# motor_driver_ver3_0.net
KiCad netlist of a schematic drawn in EAGLE
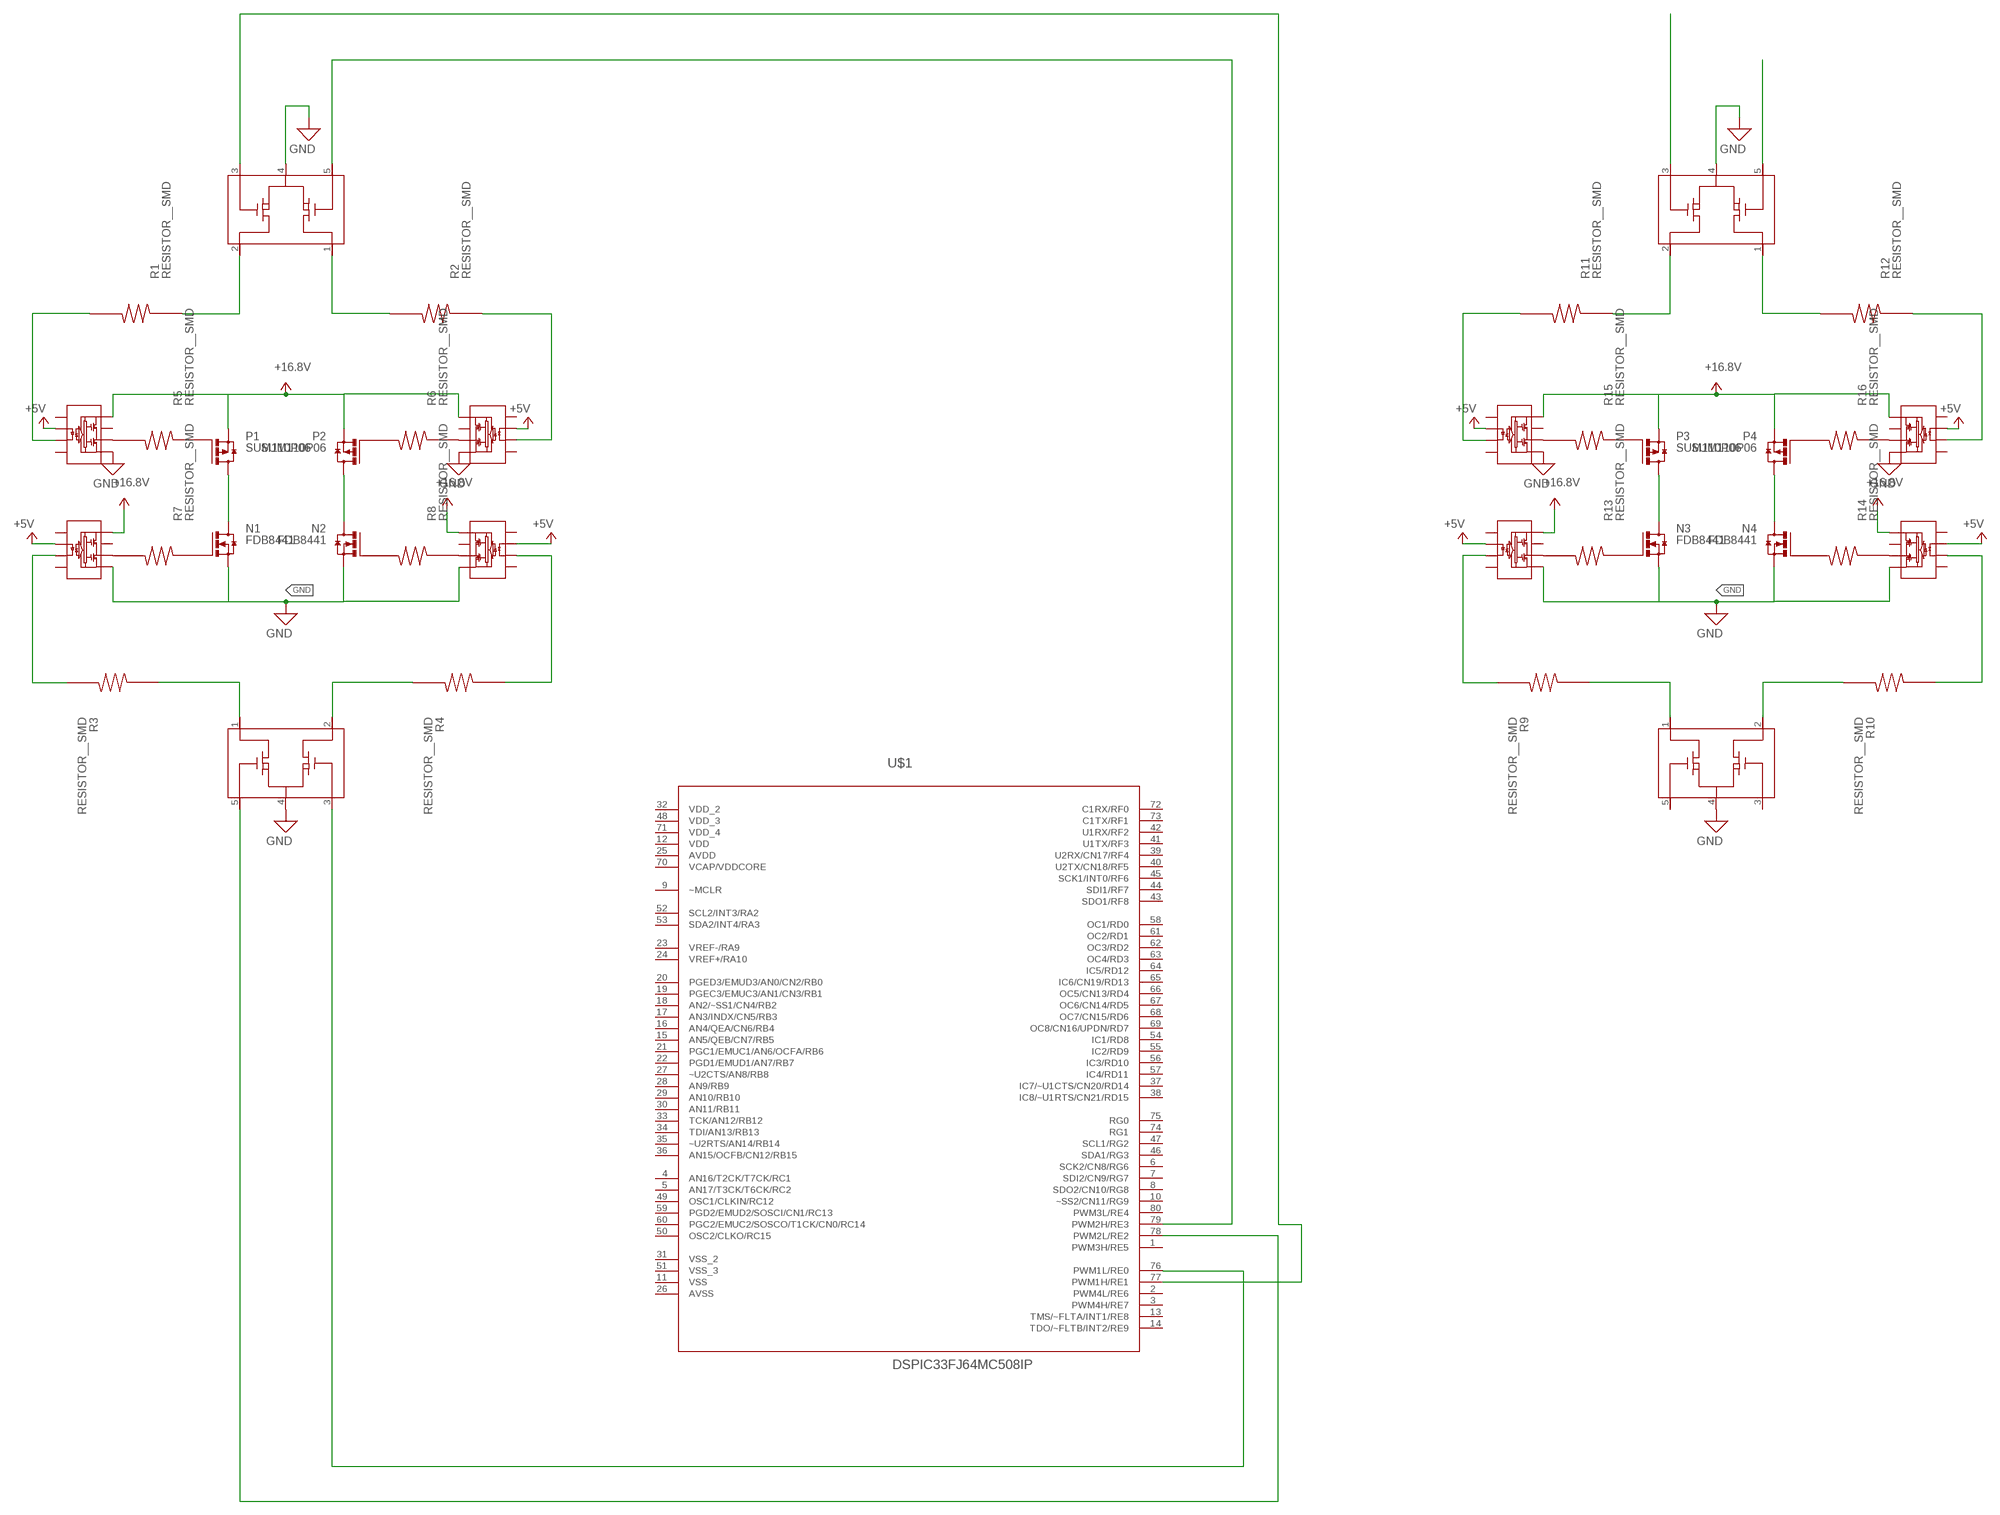
[diagram p0: schematic, sheet 1]

(export (version "E")
  (design (tool "Eeschema 10.0.6"))
  (components
    (comp (ref "F1")
      (value "CPH5617")
      (footprint "eagle-import:CHP-5")
      (libsource (lib "eagle-import") (part "CPH5617"))
    )
    (comp (ref "F2")
      (value "CPH5617")
      (footprint "eagle-import:CHP-5")
      (libsource (lib "eagle-import") (part "CPH5617"))
    )
    (comp (ref "F3")
      (value "CPH5617")
      (footprint "eagle-import:CHP-5")
      (libsource (lib "eagle-import") (part "CPH5617"))
    )
    (comp (ref "F4")
      (value "CPH5617")
      (footprint "eagle-import:CHP-5")
      (libsource (lib "eagle-import") (part "CPH5617"))
    )
    (comp (ref "IC2")
      (value "TLP351")
      (footprint "eagle-import:DIL08")
      (libsource (lib "eagle-import") (part "TLP351"))
    )
    (comp (ref "IC_L_I_D")
      (value "TLP351")
      (footprint "eagle-import:DIL08")
      (libsource (lib "eagle-import") (part "TLP351"))
    )
    (comp (ref "IC_L_I_U")
      (value "TLP351")
      (footprint "eagle-import:DIL08")
      (libsource (lib "eagle-import") (part "TLP351"))
    )
    (comp (ref "IC_L_O_D")
      (value "TLP351")
      (footprint "eagle-import:DIL08")
      (libsource (lib "eagle-import") (part "TLP351"))
    )
    (comp (ref "IC_L_O_U")
      (value "TLP351")
      (footprint "eagle-import:DIL08")
      (libsource (lib "eagle-import") (part "TLP351"))
    )
    (comp (ref "N1")
      (value "FDB8441")
      (footprint "eagle-import:TO-263")
      (libsource (lib "eagle-import") (part "FDB8441"))
    )
    (comp (ref "N2")
      (value "FDB8441")
      (footprint "eagle-import:TO-263")
      (libsource (lib "eagle-import") (part "FDB8441"))
    )
    (comp (ref "N3")
      (value "FDB8441")
      (footprint "eagle-import:TO-263")
      (libsource (lib "eagle-import") (part "FDB8441"))
    )
    (comp (ref "N4")
      (value "FDB8441")
      (footprint "eagle-import:TO-263")
      (libsource (lib "eagle-import") (part "FDB8441"))
    )
    (comp (ref "P1")
      (value "SUM110P06")
      (footprint "eagle-import:TO-263")
      (libsource (lib "eagle-import") (part "SUM110P06"))
    )
    (comp (ref "P2")
      (value "SUM110P06")
      (footprint "eagle-import:TO-263")
      (libsource (lib "eagle-import") (part "SUM110P06"))
    )
    (comp (ref "P3")
      (value "SUM110P06")
      (footprint "eagle-import:TO-263")
      (libsource (lib "eagle-import") (part "SUM110P06"))
    )
    (comp (ref "P4")
      (value "SUM110P06")
      (footprint "eagle-import:TO-263")
      (libsource (lib "eagle-import") (part "SUM110P06"))
    )
    (comp (ref "R1")
      (value "RESISTOR__SMD")
      (footprint "eagle-import:1608")
      (libsource (lib "eagle-import") (part "RESISTOR__SMD"))
    )
    (comp (ref "R2")
      (value "RESISTOR__SMD")
      (footprint "eagle-import:1608")
      (libsource (lib "eagle-import") (part "RESISTOR__SMD"))
    )
    (comp (ref "R3")
      (value "RESISTOR__SMD")
      (footprint "eagle-import:1608")
      (libsource (lib "eagle-import") (part "RESISTOR__SMD"))
    )
    (comp (ref "R4")
      (value "RESISTOR__SMD")
      (footprint "eagle-import:1608")
      (libsource (lib "eagle-import") (part "RESISTOR__SMD"))
    )
    (comp (ref "R5")
      (value "RESISTOR__SMD")
      (footprint "eagle-import:1608")
      (libsource (lib "eagle-import") (part "RESISTOR__SMD"))
    )
    (comp (ref "R6")
      (value "RESISTOR__SMD")
      (footprint "eagle-import:1608")
      (libsource (lib "eagle-import") (part "RESISTOR__SMD"))
    )
    (comp (ref "R7")
      (value "RESISTOR__SMD")
      (footprint "eagle-import:1608")
      (libsource (lib "eagle-import") (part "RESISTOR__SMD"))
    )
    (comp (ref "R8")
      (value "RESISTOR__SMD")
      (footprint "eagle-import:1608")
      (libsource (lib "eagle-import") (part "RESISTOR__SMD"))
    )
    (comp (ref "R9")
      (value "RESISTOR__SMD")
      (footprint "eagle-import:1608")
      (libsource (lib "eagle-import") (part "RESISTOR__SMD"))
    )
    (comp (ref "R10")
      (value "RESISTOR__SMD")
      (footprint "eagle-import:1608")
      (libsource (lib "eagle-import") (part "RESISTOR__SMD"))
    )
    (comp (ref "R11")
      (value "RESISTOR__SMD")
      (footprint "eagle-import:1608")
      (libsource (lib "eagle-import") (part "RESISTOR__SMD"))
    )
    (comp (ref "R12")
      (value "RESISTOR__SMD")
      (footprint "eagle-import:1608")
      (libsource (lib "eagle-import") (part "RESISTOR__SMD"))
    )
    (comp (ref "R13")
      (value "RESISTOR__SMD")
      (footprint "eagle-import:1608")
      (libsource (lib "eagle-import") (part "RESISTOR__SMD"))
    )
    (comp (ref "R14")
      (value "RESISTOR__SMD")
      (footprint "eagle-import:1608")
      (libsource (lib "eagle-import") (part "RESISTOR__SMD"))
    )
    (comp (ref "R15")
      (value "RESISTOR__SMD")
      (footprint "eagle-import:1608")
      (libsource (lib "eagle-import") (part "RESISTOR__SMD"))
    )
    (comp (ref "R16")
      (value "RESISTOR__SMD")
      (footprint "eagle-import:1608")
      (libsource (lib "eagle-import") (part "RESISTOR__SMD"))
    )
    (comp (ref "U$1")
      (value "DSPIC33FJ64MC508IP")
      (footprint "eagle-import:QFP50P1400X1400X120-80N")
      (libsource (lib "eagle-import") (part "DSPIC33FJ64MC508IP"))
    )
    (comp (ref "U$18")
      (value "TLP351")
      (footprint "eagle-import:DIL08")
      (libsource (lib "eagle-import") (part "TLP351"))
    )
    (comp (ref "U$20")
      (value "TLP351")
      (footprint "eagle-import:DIL08")
      (libsource (lib "eagle-import") (part "TLP351"))
    )
    (comp (ref "U$21")
      (value "TLP351")
      (footprint "eagle-import:DIL08")
      (libsource (lib "eagle-import") (part "TLP351"))
    )
  )
  (nets
    (net (code "1") (name "+5V") (class "Default")
      (node (ref "IC2") (pin "2") (pinfunction "LED+_2") (pintype "bidirectional"))
      (node (ref "IC_L_I_D") (pin "2") (pinfunction "LED+_2") (pintype "bidirectional"))
      (node (ref "IC_L_I_U") (pin "2") (pinfunction "LED+_2") (pintype "bidirectional"))
      (node (ref "IC_L_O_D") (pin "2") (pinfunction "LED+_2") (pintype "bidirectional"))
      (node (ref "IC_L_O_U") (pin "2") (pinfunction "LED+_2") (pintype "bidirectional"))
      (node (ref "U$18") (pin "2") (pinfunction "LED+_2") (pintype "bidirectional"))
      (node (ref "U$20") (pin "2") (pinfunction "LED+_2") (pintype "bidirectional"))
      (node (ref "U$21") (pin "2") (pinfunction "LED+_2") (pintype "bidirectional"))
    )
    (net (code "2") (name "+16.8V") (class "Default")
      (node (ref "IC2") (pin "8") (pinfunction "VDD_8") (pintype "bidirectional"))
      (node (ref "IC_L_I_D") (pin "8") (pinfunction "VDD_8") (pintype "bidirectional"))
      (node (ref "IC_L_I_U") (pin "8") (pinfunction "VDD_8") (pintype "bidirectional"))
      (node (ref "IC_L_O_D") (pin "8") (pinfunction "VDD_8") (pintype "bidirectional"))
      (node (ref "IC_L_O_U") (pin "8") (pinfunction "VDD_8") (pintype "bidirectional"))
      (node (ref "P1") (pin "2") (pinfunction "S_2") (pintype "passive"))
      (node (ref "P2") (pin "2") (pinfunction "S_2") (pintype "passive"))
      (node (ref "P3") (pin "2") (pinfunction "S_2") (pintype "passive"))
      (node (ref "P4") (pin "2") (pinfunction "S_2") (pintype "passive"))
      (node (ref "U$18") (pin "8") (pinfunction "VDD_8") (pintype "bidirectional"))
      (node (ref "U$20") (pin "8") (pinfunction "VDD_8") (pintype "bidirectional"))
      (node (ref "U$21") (pin "8") (pinfunction "VDD_8") (pintype "bidirectional"))
    )
    (net (code "3") (name "/AVDD") (class "Default")
      (node (ref "U$1") (pin "25") (pinfunction "AVDD_25") (pintype "power_in"))
    )
    (net (code "4") (name "/AVSS") (class "Default")
      (node (ref "U$1") (pin "26") (pinfunction "AVSS_26") (pintype "power_in"))
    )
    (net (code "5") (name "/VCAP{slash}VDDCORE") (class "Default")
      (node (ref "U$1") (pin "70") (pinfunction "VCAP/VDDCORE_70") (pintype "power_in"))
    )
    (net (code "6") (name "/VDD") (class "Default")
      (node (ref "U$1") (pin "12") (pinfunction "VDD_12") (pintype "power_in"))
    )
    (net (code "7") (name "/VDD_2") (class "Default")
      (node (ref "U$1") (pin "32") (pinfunction "VDD_2_32") (pintype "power_in"))
    )
    (net (code "8") (name "/VDD_3") (class "Default")
      (node (ref "U$1") (pin "48") (pinfunction "VDD_3_48") (pintype "power_in"))
    )
    (net (code "9") (name "/VDD_4") (class "Default")
      (node (ref "U$1") (pin "71") (pinfunction "VDD_4_71") (pintype "power_in"))
    )
    (net (code "10") (name "/VSS") (class "Default")
      (node (ref "U$1") (pin "11") (pinfunction "VSS_11") (pintype "power_in"))
    )
    (net (code "11") (name "/VSS_2") (class "Default")
      (node (ref "U$1") (pin "31") (pinfunction "VSS_2_31") (pintype "power_in"))
    )
    (net (code "12") (name "/VSS_3") (class "Default")
      (node (ref "U$1") (pin "51") (pinfunction "VSS_3_51") (pintype "power_in"))
    )
    (net (code "13") (name "GND") (class "Default")
      (node (ref "F1") (pin "4") (pinfunction "S_4") (pintype "bidirectional"))
      (node (ref "F2") (pin "4") (pinfunction "S_4") (pintype "bidirectional"))
      (node (ref "F3") (pin "4") (pinfunction "S_4") (pintype "bidirectional"))
      (node (ref "F4") (pin "4") (pinfunction "S_4") (pintype "bidirectional"))
      (node (ref "IC2") (pin "5") (pinfunction "GND_5") (pintype "bidirectional"))
      (node (ref "IC_L_I_D") (pin "5") (pinfunction "GND_5") (pintype "bidirectional"))
      (node (ref "IC_L_I_U") (pin "5") (pinfunction "GND_5") (pintype "bidirectional"))
      (node (ref "IC_L_O_D") (pin "5") (pinfunction "GND_5") (pintype "bidirectional"))
      (node (ref "IC_L_O_U") (pin "5") (pinfunction "GND_5") (pintype "bidirectional"))
      (node (ref "N1") (pin "2") (pinfunction "S_2") (pintype "passive"))
      (node (ref "N2") (pin "2") (pinfunction "S_2") (pintype "passive"))
      (node (ref "N3") (pin "2") (pinfunction "S_2") (pintype "passive"))
      (node (ref "N4") (pin "2") (pinfunction "S_2") (pintype "passive"))
      (node (ref "U$18") (pin "5") (pinfunction "GND_5") (pintype "bidirectional"))
      (node (ref "U$20") (pin "5") (pinfunction "GND_5") (pintype "bidirectional"))
      (node (ref "U$21") (pin "5") (pinfunction "GND_5") (pintype "bidirectional"))
    )
    (net (code "14") (name "Net-(F1-D1)") (class "Default")
      (node (ref "F1") (pin "1") (pinfunction "D1_1") (pintype "bidirectional"))
      (node (ref "R2") (pin "2") (pinfunction "P$2_2") (pintype "passive"))
    )
    (net (code "15") (name "Net-(F1-D2)") (class "Default")
      (node (ref "F1") (pin "2") (pinfunction "D2_2") (pintype "bidirectional"))
      (node (ref "R1") (pin "1") (pinfunction "P$1_1") (pintype "passive"))
    )
    (net (code "16") (name "Net-(F1-G1)") (class "Default")
      (node (ref "F1") (pin "5") (pinfunction "G1_5") (pintype "bidirectional"))
      (node (ref "U$1") (pin "79") (pinfunction "PWM2H/RE3_79") (pintype "bidirectional"))
    )
    (net (code "17") (name "Net-(F1-G2)") (class "Default")
      (node (ref "F1") (pin "3") (pinfunction "G2_3") (pintype "bidirectional"))
      (node (ref "U$1") (pin "77") (pinfunction "PWM1H/RE1_77") (pintype "bidirectional"))
    )
    (net (code "18") (name "Net-(F2-D1)") (class "Default")
      (node (ref "F2") (pin "1") (pinfunction "D1_1") (pintype "bidirectional"))
      (node (ref "R3") (pin "2") (pinfunction "P$2_2") (pintype "passive"))
    )
    (net (code "19") (name "Net-(F2-D2)") (class "Default")
      (node (ref "F2") (pin "2") (pinfunction "D2_2") (pintype "bidirectional"))
      (node (ref "R4") (pin "1") (pinfunction "P$1_1") (pintype "passive"))
    )
    (net (code "20") (name "Net-(F2-G1)") (class "Default")
      (node (ref "F2") (pin "5") (pinfunction "G1_5") (pintype "bidirectional"))
      (node (ref "U$1") (pin "78") (pinfunction "PWM2L/RE2_78") (pintype "bidirectional"))
    )
    (net (code "21") (name "Net-(F2-G2)") (class "Default")
      (node (ref "F2") (pin "3") (pinfunction "G2_3") (pintype "bidirectional"))
      (node (ref "U$1") (pin "76") (pinfunction "PWM1L/RE0_76") (pintype "bidirectional"))
    )
    (net (code "22") (name "Net-(F3-D1)") (class "Default")
      (node (ref "F3") (pin "1") (pinfunction "D1_1") (pintype "bidirectional"))
      (node (ref "R12") (pin "2") (pinfunction "P$2_2") (pintype "passive"))
    )
    (net (code "23") (name "Net-(F3-D2)") (class "Default")
      (node (ref "F3") (pin "2") (pinfunction "D2_2") (pintype "bidirectional"))
      (node (ref "R11") (pin "1") (pinfunction "P$1_1") (pintype "passive"))
    )
    (net (code "24") (name "Net-(F4-D1)") (class "Default")
      (node (ref "F4") (pin "1") (pinfunction "D1_1") (pintype "bidirectional"))
      (node (ref "R9") (pin "2") (pinfunction "P$2_2") (pintype "passive"))
    )
    (net (code "25") (name "Net-(F4-D2)") (class "Default")
      (node (ref "F4") (pin "2") (pinfunction "D2_2") (pintype "bidirectional"))
      (node (ref "R10") (pin "1") (pinfunction "P$1_1") (pintype "passive"))
    )
    (net (code "26") (name "Net-(IC2-LED-)") (class "Default")
      (node (ref "IC2") (pin "3") (pinfunction "LED-_3") (pintype "bidirectional"))
      (node (ref "R11") (pin "2") (pinfunction "P$2_2") (pintype "passive"))
    )
    (net (code "27") (name "Net-(IC2-OUT)") (class "Default")
      (node (ref "IC2") (pin "6") (pinfunction "OUT_6") (pintype "output"))
      (node (ref "R15") (pin "2") (pinfunction "P$2_2") (pintype "passive"))
    )
    (net (code "28") (name "Net-(IC_L_I_D-LED-)") (class "Default")
      (node (ref "IC_L_I_D") (pin "3") (pinfunction "LED-_3") (pintype "bidirectional"))
      (node (ref "R4") (pin "2") (pinfunction "P$2_2") (pintype "passive"))
    )
    (net (code "29") (name "Net-(IC_L_I_D-OUT)") (class "Default")
      (node (ref "IC_L_I_D") (pin "6") (pinfunction "OUT_6") (pintype "output"))
      (node (ref "R8") (pin "1") (pinfunction "P$1_1") (pintype "passive"))
    )
    (net (code "30") (name "Net-(IC_L_I_U-LED-)") (class "Default")
      (node (ref "IC_L_I_U") (pin "3") (pinfunction "LED-_3") (pintype "bidirectional"))
      (node (ref "R2") (pin "1") (pinfunction "P$1_1") (pintype "passive"))
    )
    (net (code "31") (name "Net-(IC_L_I_U-OUT)") (class "Default")
      (node (ref "IC_L_I_U") (pin "6") (pinfunction "OUT_6") (pintype "output"))
      (node (ref "R6") (pin "1") (pinfunction "P$1_1") (pintype "passive"))
    )
    (net (code "32") (name "Net-(IC_L_O_D-LED-)") (class "Default")
      (node (ref "IC_L_O_D") (pin "3") (pinfunction "LED-_3") (pintype "bidirectional"))
      (node (ref "R3") (pin "1") (pinfunction "P$1_1") (pintype "passive"))
    )
    (net (code "33") (name "Net-(IC_L_O_D-OUT)") (class "Default")
      (node (ref "IC_L_O_D") (pin "6") (pinfunction "OUT_6") (pintype "output"))
      (node (ref "R7") (pin "2") (pinfunction "P$2_2") (pintype "passive"))
    )
    (net (code "34") (name "Net-(IC_L_O_U-LED-)") (class "Default")
      (node (ref "IC_L_O_U") (pin "3") (pinfunction "LED-_3") (pintype "bidirectional"))
      (node (ref "R1") (pin "2") (pinfunction "P$2_2") (pintype "passive"))
    )
    (net (code "35") (name "Net-(IC_L_O_U-OUT)") (class "Default")
      (node (ref "IC_L_O_U") (pin "6") (pinfunction "OUT_6") (pintype "output"))
      (node (ref "R5") (pin "2") (pinfunction "P$2_2") (pintype "passive"))
    )
    (net (code "36") (name "Net-(N1-D)") (class "Default")
      (node (ref "N1") (pin "3") (pinfunction "D_3") (pintype "passive"))
      (node (ref "P1") (pin "3") (pinfunction "D_3") (pintype "passive"))
    )
    (net (code "37") (name "Net-(N1-G)") (class "Default")
      (node (ref "N1") (pin "1") (pinfunction "G_1") (pintype "passive"))
      (node (ref "R7") (pin "1") (pinfunction "P$1_1") (pintype "passive"))
    )
    (net (code "38") (name "Net-(N2-D)") (class "Default")
      (node (ref "N2") (pin "3") (pinfunction "D_3") (pintype "passive"))
      (node (ref "P2") (pin "3") (pinfunction "D_3") (pintype "passive"))
    )
    (net (code "39") (name "Net-(N2-G)") (class "Default")
      (node (ref "N2") (pin "1") (pinfunction "G_1") (pintype "passive"))
      (node (ref "R8") (pin "2") (pinfunction "P$2_2") (pintype "passive"))
    )
    (net (code "40") (name "Net-(N3-D)") (class "Default")
      (node (ref "N3") (pin "3") (pinfunction "D_3") (pintype "passive"))
      (node (ref "P3") (pin "3") (pinfunction "D_3") (pintype "passive"))
    )
    (net (code "41") (name "Net-(N3-G)") (class "Default")
      (node (ref "N3") (pin "1") (pinfunction "G_1") (pintype "passive"))
      (node (ref "R13") (pin "1") (pinfunction "P$1_1") (pintype "passive"))
    )
    (net (code "42") (name "Net-(N4-D)") (class "Default")
      (node (ref "N4") (pin "3") (pinfunction "D_3") (pintype "passive"))
      (node (ref "P4") (pin "3") (pinfunction "D_3") (pintype "passive"))
    )
    (net (code "43") (name "Net-(N4-G)") (class "Default")
      (node (ref "N4") (pin "1") (pinfunction "G_1") (pintype "passive"))
      (node (ref "R14") (pin "2") (pinfunction "P$2_2") (pintype "passive"))
    )
    (net (code "44") (name "Net-(P1-G)") (class "Default")
      (node (ref "P1") (pin "1") (pinfunction "G_1") (pintype "passive"))
      (node (ref "R5") (pin "1") (pinfunction "P$1_1") (pintype "passive"))
    )
    (net (code "45") (name "Net-(P2-G)") (class "Default")
      (node (ref "P2") (pin "1") (pinfunction "G_1") (pintype "passive"))
      (node (ref "R6") (pin "2") (pinfunction "P$2_2") (pintype "passive"))
    )
    (net (code "46") (name "Net-(P3-G)") (class "Default")
      (node (ref "P3") (pin "1") (pinfunction "G_1") (pintype "passive"))
      (node (ref "R15") (pin "1") (pinfunction "P$1_1") (pintype "passive"))
    )
    (net (code "47") (name "Net-(P4-G)") (class "Default")
      (node (ref "P4") (pin "1") (pinfunction "G_1") (pintype "passive"))
      (node (ref "R16") (pin "2") (pinfunction "P$2_2") (pintype "passive"))
    )
    (net (code "48") (name "Net-(R9-P$1)") (class "Default")
      (node (ref "R9") (pin "1") (pinfunction "P$1_1") (pintype "passive"))
      (node (ref "U$20") (pin "3") (pinfunction "LED-_3") (pintype "bidirectional"))
    )
    (net (code "49") (name "Net-(R10-P$2)") (class "Default")
      (node (ref "R10") (pin "2") (pinfunction "P$2_2") (pintype "passive"))
      (node (ref "U$21") (pin "3") (pinfunction "LED-_3") (pintype "bidirectional"))
    )
    (net (code "50") (name "Net-(R12-P$1)") (class "Default")
      (node (ref "R12") (pin "1") (pinfunction "P$1_1") (pintype "passive"))
      (node (ref "U$18") (pin "3") (pinfunction "LED-_3") (pintype "bidirectional"))
    )
    (net (code "51") (name "Net-(R13-P$2)") (class "Default")
      (node (ref "R13") (pin "2") (pinfunction "P$2_2") (pintype "passive"))
      (node (ref "U$20") (pin "6") (pinfunction "OUT_6") (pintype "output"))
    )
    (net (code "52") (name "Net-(R14-P$1)") (class "Default")
      (node (ref "R14") (pin "1") (pinfunction "P$1_1") (pintype "passive"))
      (node (ref "U$21") (pin "6") (pinfunction "OUT_6") (pintype "output"))
    )
    (net (code "53") (name "Net-(R16-P$1)") (class "Default")
      (node (ref "R16") (pin "1") (pinfunction "P$1_1") (pintype "passive"))
      (node (ref "U$18") (pin "6") (pinfunction "OUT_6") (pintype "output"))
    )
    (net (code "54") (name "unconnected-(F3-G1-Pad5)") (class "Default")
      (node (ref "F3") (pin "5") (pinfunction "G1_5") (pintype "bidirectional"))
    )
    (net (code "55") (name "unconnected-(F3-G2-Pad3)") (class "Default")
      (node (ref "F3") (pin "3") (pinfunction "G2_3") (pintype "bidirectional"))
    )
    (net (code "56") (name "unconnected-(F4-G1-Pad5)") (class "Default")
      (node (ref "F4") (pin "5") (pinfunction "G1_5") (pintype "bidirectional"))
    )
    (net (code "57") (name "unconnected-(F4-G2-Pad3)") (class "Default")
      (node (ref "F4") (pin "3") (pinfunction "G2_3") (pintype "bidirectional"))
    )
    (net (code "58") (name "unconnected-(IC2-NC1-Pad1)") (class "Default")
      (node (ref "IC2") (pin "1") (pinfunction "NC1_1") (pintype "no_connect"))
    )
    (net (code "59") (name "unconnected-(IC2-NC4-Pad4)") (class "Default")
      (node (ref "IC2") (pin "4") (pinfunction "NC4_4") (pintype "no_connect"))
    )
    (net (code "60") (name "unconnected-(IC2-NC7-Pad7)") (class "Default")
      (node (ref "IC2") (pin "7") (pinfunction "NC7_7") (pintype "no_connect"))
    )
    (net (code "61") (name "unconnected-(IC_L_I_D-NC1-Pad1)") (class "Default")
      (node (ref "IC_L_I_D") (pin "1") (pinfunction "NC1_1") (pintype "no_connect"))
    )
    (net (code "62") (name "unconnected-(IC_L_I_D-NC4-Pad4)") (class "Default")
      (node (ref "IC_L_I_D") (pin "4") (pinfunction "NC4_4") (pintype "no_connect"))
    )
    (net (code "63") (name "unconnected-(IC_L_I_D-NC7-Pad7)") (class "Default")
      (node (ref "IC_L_I_D") (pin "7") (pinfunction "NC7_7") (pintype "no_connect"))
    )
    (net (code "64") (name "unconnected-(IC_L_I_U-NC1-Pad1)") (class "Default")
      (node (ref "IC_L_I_U") (pin "1") (pinfunction "NC1_1") (pintype "no_connect"))
    )
    (net (code "65") (name "unconnected-(IC_L_I_U-NC4-Pad4)") (class "Default")
      (node (ref "IC_L_I_U") (pin "4") (pinfunction "NC4_4") (pintype "no_connect"))
    )
    (net (code "66") (name "unconnected-(IC_L_I_U-NC7-Pad7)") (class "Default")
      (node (ref "IC_L_I_U") (pin "7") (pinfunction "NC7_7") (pintype "no_connect"))
    )
    (net (code "67") (name "unconnected-(IC_L_O_D-NC1-Pad1)") (class "Default")
      (node (ref "IC_L_O_D") (pin "1") (pinfunction "NC1_1") (pintype "no_connect"))
    )
    (net (code "68") (name "unconnected-(IC_L_O_D-NC4-Pad4)") (class "Default")
      (node (ref "IC_L_O_D") (pin "4") (pinfunction "NC4_4") (pintype "no_connect"))
    )
    (net (code "69") (name "unconnected-(IC_L_O_D-NC7-Pad7)") (class "Default")
      (node (ref "IC_L_O_D") (pin "7") (pinfunction "NC7_7") (pintype "no_connect"))
    )
    (net (code "70") (name "unconnected-(IC_L_O_U-NC1-Pad1)") (class "Default")
      (node (ref "IC_L_O_U") (pin "1") (pinfunction "NC1_1") (pintype "no_connect"))
    )
    (net (code "71") (name "unconnected-(IC_L_O_U-NC4-Pad4)") (class "Default")
      (node (ref "IC_L_O_U") (pin "4") (pinfunction "NC4_4") (pintype "no_connect"))
    )
    (net (code "72") (name "unconnected-(IC_L_O_U-NC7-Pad7)") (class "Default")
      (node (ref "IC_L_O_U") (pin "7") (pinfunction "NC7_7") (pintype "no_connect"))
    )
    (net (code "73") (name "unconnected-(U$1-AN2{slash}~{SS1{slash}CN4{slash}RB2}-Pad18)") (class "Default")
      (node (ref "U$1") (pin "18") (pinfunction "AN2/~{SS1/CN4/RB2}_18") (pintype "bidirectional"))
    )
    (net (code "74") (name "unconnected-(U$1-AN3{slash}INDX{slash}CN5{slash}RB3-Pad17)") (class "Default")
      (node (ref "U$1") (pin "17") (pinfunction "AN3/INDX/CN5/RB3_17") (pintype "bidirectional"))
    )
    (net (code "75") (name "unconnected-(U$1-AN4{slash}QEA{slash}CN6{slash}RB4-Pad16)") (class "Default")
      (node (ref "U$1") (pin "16") (pinfunction "AN4/QEA/CN6/RB4_16") (pintype "bidirectional"))
    )
    (net (code "76") (name "unconnected-(U$1-AN5{slash}QEB{slash}CN7{slash}RB5-Pad15)") (class "Default")
      (node (ref "U$1") (pin "15") (pinfunction "AN5/QEB/CN7/RB5_15") (pintype "bidirectional"))
    )
    (net (code "77") (name "unconnected-(U$1-AN9{slash}RB9-Pad28)") (class "Default")
      (node (ref "U$1") (pin "28") (pinfunction "AN9/RB9_28") (pintype "bidirectional"))
    )
    (net (code "78") (name "unconnected-(U$1-AN10{slash}RB10-Pad29)") (class "Default")
      (node (ref "U$1") (pin "29") (pinfunction "AN10/RB10_29") (pintype "bidirectional"))
    )
    (net (code "79") (name "unconnected-(U$1-AN11{slash}RB11-Pad30)") (class "Default")
      (node (ref "U$1") (pin "30") (pinfunction "AN11/RB11_30") (pintype "bidirectional"))
    )
    (net (code "80") (name "unconnected-(U$1-AN15{slash}OCFB{slash}CN12{slash}RB15-Pad36)") (class "Default")
      (node (ref "U$1") (pin "36") (pinfunction "AN15/OCFB/CN12/RB15_36") (pintype "bidirectional"))
    )
    (net (code "81") (name "unconnected-(U$1-AN16{slash}T2CK{slash}T7CK{slash}RC1-Pad4)") (class "Default")
      (node (ref "U$1") (pin "4") (pinfunction "AN16/T2CK/T7CK/RC1_4") (pintype "bidirectional"))
    )
    (net (code "82") (name "unconnected-(U$1-AN17{slash}T3CK{slash}T6CK{slash}RC2-Pad5)") (class "Default")
      (node (ref "U$1") (pin "5") (pinfunction "AN17/T3CK/T6CK/RC2_5") (pintype "bidirectional"))
    )
    (net (code "83") (name "unconnected-(U$1-C1RX{slash}RF0-Pad72)") (class "Default")
      (node (ref "U$1") (pin "72") (pinfunction "C1RX/RF0_72") (pintype "bidirectional"))
    )
    (net (code "84") (name "unconnected-(U$1-C1TX{slash}RF1-Pad73)") (class "Default")
      (node (ref "U$1") (pin "73") (pinfunction "C1TX/RF1_73") (pintype "bidirectional"))
    )
    (net (code "85") (name "unconnected-(U$1-IC1{slash}RD8-Pad54)") (class "Default")
      (node (ref "U$1") (pin "54") (pinfunction "IC1/RD8_54") (pintype "bidirectional"))
    )
    (net (code "86") (name "unconnected-(U$1-IC2{slash}RD9-Pad55)") (class "Default")
      (node (ref "U$1") (pin "55") (pinfunction "IC2/RD9_55") (pintype "bidirectional"))
    )
    (net (code "87") (name "unconnected-(U$1-IC3{slash}RD10-Pad56)") (class "Default")
      (node (ref "U$1") (pin "56") (pinfunction "IC3/RD10_56") (pintype "bidirectional"))
    )
    (net (code "88") (name "unconnected-(U$1-IC4{slash}RD11-Pad57)") (class "Default")
      (node (ref "U$1") (pin "57") (pinfunction "IC4/RD11_57") (pintype "bidirectional"))
    )
    (net (code "89") (name "unconnected-(U$1-IC5{slash}RD12-Pad64)") (class "Default")
      (node (ref "U$1") (pin "64") (pinfunction "IC5/RD12_64") (pintype "bidirectional"))
    )
    (net (code "90") (name "unconnected-(U$1-IC6{slash}CN19{slash}RD13-Pad65)") (class "Default")
      (node (ref "U$1") (pin "65") (pinfunction "IC6/CN19/RD13_65") (pintype "bidirectional"))
    )
    (net (code "91") (name "unconnected-(U$1-IC7{slash}~{U1CTS{slash}CN20{slash}RD14}-Pad37)") (class "Default")
      (node (ref "U$1") (pin "37") (pinfunction "IC7/~{U1CTS/CN20/RD14}_37") (pintype "bidirectional"))
    )
    (net (code "92") (name "unconnected-(U$1-IC8{slash}~{U1RTS{slash}CN21{slash}RD15}-Pad38)") (class "Default")
      (node (ref "U$1") (pin "38") (pinfunction "IC8/~{U1RTS/CN21/RD15}_38") (pintype "bidirectional"))
    )
    (net (code "93") (name "unconnected-(U$1-OC1{slash}RD0-Pad58)") (class "Default")
      (node (ref "U$1") (pin "58") (pinfunction "OC1/RD0_58") (pintype "bidirectional"))
    )
    (net (code "94") (name "unconnected-(U$1-OC2{slash}RD1-Pad61)") (class "Default")
      (node (ref "U$1") (pin "61") (pinfunction "OC2/RD1_61") (pintype "bidirectional"))
    )
    (net (code "95") (name "unconnected-(U$1-OC3{slash}RD2-Pad62)") (class "Default")
      (node (ref "U$1") (pin "62") (pinfunction "OC3/RD2_62") (pintype "bidirectional"))
    )
    (net (code "96") (name "unconnected-(U$1-OC4{slash}RD3-Pad63)") (class "Default")
      (node (ref "U$1") (pin "63") (pinfunction "OC4/RD3_63") (pintype "bidirectional"))
    )
    (net (code "97") (name "unconnected-(U$1-OC5{slash}CN13{slash}RD4-Pad66)") (class "Default")
      (node (ref "U$1") (pin "66") (pinfunction "OC5/CN13/RD4_66") (pintype "bidirectional"))
    )
    (net (code "98") (name "unconnected-(U$1-OC6{slash}CN14{slash}RD5-Pad67)") (class "Default")
      (node (ref "U$1") (pin "67") (pinfunction "OC6/CN14/RD5_67") (pintype "bidirectional"))
    )
    (net (code "99") (name "unconnected-(U$1-OC7{slash}CN15{slash}RD6-Pad68)") (class "Default")
      (node (ref "U$1") (pin "68") (pinfunction "OC7/CN15/RD6_68") (pintype "bidirectional"))
    )
    (net (code "100") (name "unconnected-(U$1-OC8{slash}CN16{slash}UPDN{slash}RD7-Pad69)") (class "Default")
      (node (ref "U$1") (pin "69") (pinfunction "OC8/CN16/UPDN/RD7_69") (pintype "bidirectional"))
    )
    (net (code "101") (name "unconnected-(U$1-OSC1{slash}CLKIN{slash}RC12-Pad49)") (class "Default")
      (node (ref "U$1") (pin "49") (pinfunction "OSC1/CLKIN/RC12_49") (pintype "bidirectional"))
    )
    (net (code "102") (name "unconnected-(U$1-OSC2{slash}CLKO{slash}RC15-Pad50)") (class "Default")
      (node (ref "U$1") (pin "50") (pinfunction "OSC2/CLKO/RC15_50") (pintype "bidirectional"))
    )
    (net (code "103") (name "unconnected-(U$1-PGC1{slash}EMUC1{slash}AN6{slash}OCFA{slash}RB6-Pad21)") (class "Default")
      (node (ref "U$1") (pin "21") (pinfunction "PGC1/EMUC1/AN6/OCFA/RB6_21") (pintype "bidirectional"))
    )
    (net (code "104") (name "unconnected-(U$1-PGC2{slash}EMUC2{slash}SOSCO{slash}T1CK{slash}CN0{slash}RC14-Pad60)") (class "Default")
      (node (ref "U$1") (pin "60") (pinfunction "PGC2/EMUC2/SOSCO/T1CK/CN0/RC14_60") (pintype "bidirectional"))
    )
    (net (code "105") (name "unconnected-(U$1-PGD1{slash}EMUD1{slash}AN7{slash}RB7-Pad22)") (class "Default")
      (node (ref "U$1") (pin "22") (pinfunction "PGD1/EMUD1/AN7/RB7_22") (pintype "bidirectional"))
    )
    (net (code "106") (name "unconnected-(U$1-PGD2{slash}EMUD2{slash}SOSCI{slash}CN1{slash}RC13-Pad59)") (class "Default")
      (node (ref "U$1") (pin "59") (pinfunction "PGD2/EMUD2/SOSCI/CN1/RC13_59") (pintype "bidirectional"))
    )
    (net (code "107") (name "unconnected-(U$1-PGEC3{slash}EMUC3{slash}AN1{slash}CN3{slash}RB1-Pad19)") (class "Default")
      (node (ref "U$1") (pin "19") (pinfunction "PGEC3/EMUC3/AN1/CN3/RB1_19") (pintype "bidirectional"))
    )
    (net (code "108") (name "unconnected-(U$1-PGED3{slash}EMUD3{slash}AN0{slash}CN2{slash}RB0-Pad20)") (class "Default")
      (node (ref "U$1") (pin "20") (pinfunction "PGED3/EMUD3/AN0/CN2/RB0_20") (pintype "bidirectional"))
    )
    (net (code "109") (name "unconnected-(U$1-PWM3H{slash}RE5-Pad1)") (class "Default")
      (node (ref "U$1") (pin "1") (pinfunction "PWM3H/RE5_1") (pintype "bidirectional"))
    )
    (net (code "110") (name "unconnected-(U$1-PWM3L{slash}RE4-Pad80)") (class "Default")
      (node (ref "U$1") (pin "80") (pinfunction "PWM3L/RE4_80") (pintype "bidirectional"))
    )
    (net (code "111") (name "unconnected-(U$1-PWM4H{slash}RE7-Pad3)") (class "Default")
      (node (ref "U$1") (pin "3") (pinfunction "PWM4H/RE7_3") (pintype "bidirectional"))
    )
    (net (code "112") (name "unconnected-(U$1-PWM4L{slash}RE6-Pad2)") (class "Default")
      (node (ref "U$1") (pin "2") (pinfunction "PWM4L/RE6_2") (pintype "bidirectional"))
    )
    (net (code "113") (name "unconnected-(U$1-RG0-Pad75)") (class "Default")
      (node (ref "U$1") (pin "75") (pinfunction "RG0_75") (pintype "bidirectional"))
    )
    (net (code "114") (name "unconnected-(U$1-RG1-Pad74)") (class "Default")
      (node (ref "U$1") (pin "74") (pinfunction "RG1_74") (pintype "bidirectional"))
    )
    (net (code "115") (name "unconnected-(U$1-SCK1{slash}INT0{slash}RF6-Pad45)") (class "Default")
      (node (ref "U$1") (pin "45") (pinfunction "SCK1/INT0/RF6_45") (pintype "bidirectional"))
    )
    (net (code "116") (name "unconnected-(U$1-SCK2{slash}CN8{slash}RG6-Pad6)") (class "Default")
      (node (ref "U$1") (pin "6") (pinfunction "SCK2/CN8/RG6_6") (pintype "bidirectional"))
    )
    (net (code "117") (name "unconnected-(U$1-SCL1{slash}RG2-Pad47)") (class "Default")
      (node (ref "U$1") (pin "47") (pinfunction "SCL1/RG2_47") (pintype "bidirectional"))
    )
    (net (code "118") (name "unconnected-(U$1-SCL2{slash}INT3{slash}RA2-Pad52)") (class "Default")
      (node (ref "U$1") (pin "52") (pinfunction "SCL2/INT3/RA2_52") (pintype "bidirectional"))
    )
    (net (code "119") (name "unconnected-(U$1-SDA1{slash}RG3-Pad46)") (class "Default")
      (node (ref "U$1") (pin "46") (pinfunction "SDA1/RG3_46") (pintype "bidirectional"))
    )
    (net (code "120") (name "unconnected-(U$1-SDA2{slash}INT4{slash}RA3-Pad53)") (class "Default")
      (node (ref "U$1") (pin "53") (pinfunction "SDA2/INT4/RA3_53") (pintype "bidirectional"))
    )
    (net (code "121") (name "unconnected-(U$1-SDI1{slash}RF7-Pad44)") (class "Default")
      (node (ref "U$1") (pin "44") (pinfunction "SDI1/RF7_44") (pintype "bidirectional"))
    )
    (net (code "122") (name "unconnected-(U$1-SDI2{slash}CN9{slash}RG7-Pad7)") (class "Default")
      (node (ref "U$1") (pin "7") (pinfunction "SDI2/CN9/RG7_7") (pintype "bidirectional"))
    )
    (net (code "123") (name "unconnected-(U$1-SDO1{slash}RF8-Pad43)") (class "Default")
      (node (ref "U$1") (pin "43") (pinfunction "SDO1/RF8_43") (pintype "bidirectional"))
    )
    (net (code "124") (name "unconnected-(U$1-SDO2{slash}CN10{slash}RG8-Pad8)") (class "Default")
      (node (ref "U$1") (pin "8") (pinfunction "SDO2/CN10/RG8_8") (pintype "bidirectional"))
    )
    (net (code "125") (name "unconnected-(U$1-TCK{slash}AN12{slash}RB12-Pad33)") (class "Default")
      (node (ref "U$1") (pin "33") (pinfunction "TCK/AN12/RB12_33") (pintype "bidirectional"))
    )
    (net (code "126") (name "unconnected-(U$1-TDI{slash}AN13{slash}RB13-Pad34)") (class "Default")
      (node (ref "U$1") (pin "34") (pinfunction "TDI/AN13/RB13_34") (pintype "bidirectional"))
    )
    (net (code "127") (name "unconnected-(U$1-TDO{slash}~{FLTB{slash}INT2{slash}RE9}-Pad14)") (class "Default")
      (node (ref "U$1") (pin "14") (pinfunction "TDO/~{FLTB/INT2/RE9}_14") (pintype "bidirectional"))
    )
    (net (code "128") (name "unconnected-(U$1-TMS{slash}~{FLTA{slash}INT1{slash}RE8}-Pad13)") (class "Default")
      (node (ref "U$1") (pin "13") (pinfunction "TMS/~{FLTA/INT1/RE8}_13") (pintype "bidirectional"))
    )
    (net (code "129") (name "unconnected-(U$1-U1RX{slash}RF2-Pad42)") (class "Default")
      (node (ref "U$1") (pin "42") (pinfunction "U1RX/RF2_42") (pintype "bidirectional"))
    )
    (net (code "130") (name "unconnected-(U$1-U1TX{slash}RF3-Pad41)") (class "Default")
      (node (ref "U$1") (pin "41") (pinfunction "U1TX/RF3_41") (pintype "bidirectional"))
    )
    (net (code "131") (name "unconnected-(U$1-U2RX{slash}CN17{slash}RF4-Pad39)") (class "Default")
      (node (ref "U$1") (pin "39") (pinfunction "U2RX/CN17/RF4_39") (pintype "bidirectional"))
    )
    (net (code "132") (name "unconnected-(U$1-U2TX{slash}CN18{slash}RF5-Pad40)") (class "Default")
      (node (ref "U$1") (pin "40") (pinfunction "U2TX/CN18/RF5_40") (pintype "bidirectional"))
    )
    (net (code "133") (name "unconnected-(U$1-VREF+{slash}RA10-Pad24)") (class "Default")
      (node (ref "U$1") (pin "24") (pinfunction "VREF+/RA10_24") (pintype "bidirectional"))
    )
    (net (code "134") (name "unconnected-(U$1-VREF-{slash}RA9-Pad23)") (class "Default")
      (node (ref "U$1") (pin "23") (pinfunction "VREF-/RA9_23") (pintype "bidirectional"))
    )
    (net (code "135") (name "unconnected-(U$1-~{MCLR}-Pad9)") (class "Default")
      (node (ref "U$1") (pin "9") (pinfunction "~{MCLR}_9") (pintype "input"))
    )
    (net (code "136") (name "unconnected-(U$1-~{SS2{slash}CN11{slash}RG9}-Pad10)") (class "Default")
      (node (ref "U$1") (pin "10") (pinfunction "~{SS2/CN11/RG9}_10") (pintype "bidirectional"))
    )
    (net (code "137") (name "unconnected-(U$1-~{U2CTS{slash}AN8{slash}RB8}-Pad27)") (class "Default")
      (node (ref "U$1") (pin "27") (pinfunction "~{U2CTS/AN8/RB8}_27") (pintype "bidirectional"))
    )
    (net (code "138") (name "unconnected-(U$1-~{U2RTS{slash}AN14{slash}RB14}-Pad35)") (class "Default")
      (node (ref "U$1") (pin "35") (pinfunction "~{U2RTS/AN14/RB14}_35") (pintype "bidirectional"))
    )
    (net (code "139") (name "unconnected-(U$18-NC1-Pad1)") (class "Default")
      (node (ref "U$18") (pin "1") (pinfunction "NC1_1") (pintype "no_connect"))
    )
    (net (code "140") (name "unconnected-(U$18-NC4-Pad4)") (class "Default")
      (node (ref "U$18") (pin "4") (pinfunction "NC4_4") (pintype "no_connect"))
    )
    (net (code "141") (name "unconnected-(U$18-NC7-Pad7)") (class "Default")
      (node (ref "U$18") (pin "7") (pinfunction "NC7_7") (pintype "no_connect"))
    )
    (net (code "142") (name "unconnected-(U$20-NC1-Pad1)") (class "Default")
      (node (ref "U$20") (pin "1") (pinfunction "NC1_1") (pintype "no_connect"))
    )
    (net (code "143") (name "unconnected-(U$20-NC4-Pad4)") (class "Default")
      (node (ref "U$20") (pin "4") (pinfunction "NC4_4") (pintype "no_connect"))
    )
    (net (code "144") (name "unconnected-(U$20-NC7-Pad7)") (class "Default")
      (node (ref "U$20") (pin "7") (pinfunction "NC7_7") (pintype "no_connect"))
    )
    (net (code "145") (name "unconnected-(U$21-NC1-Pad1)") (class "Default")
      (node (ref "U$21") (pin "1") (pinfunction "NC1_1") (pintype "no_connect"))
    )
    (net (code "146") (name "unconnected-(U$21-NC4-Pad4)") (class "Default")
      (node (ref "U$21") (pin "4") (pinfunction "NC4_4") (pintype "no_connect"))
    )
    (net (code "147") (name "unconnected-(U$21-NC7-Pad7)") (class "Default")
      (node (ref "U$21") (pin "7") (pinfunction "NC7_7") (pintype "no_connect"))
    )
  )
)
